# Power.net
KiCad netlist of a schematic drawn in Altium Designer
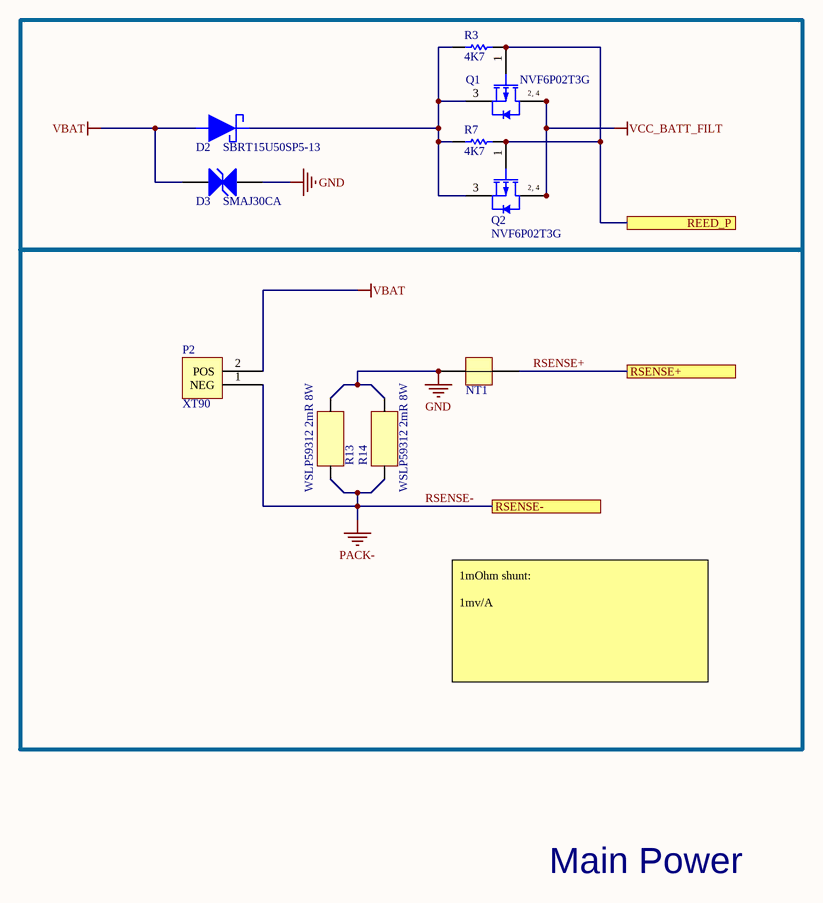
[diagram p0: Power.SchDoc]

(export (version "E")
  (design (tool "Eeschema 10.0.6"))
  (components
    (comp (ref "D2")
      (value "SBRT15U50SP5-13")
      (footprint "SBRT15U50SP5-13")
      (fields (field (name "MANUFACTURER") "Diodes Incorporated"))
      (libsource (lib "CMR_Miscellaneous_Devices") (part "SBRT15U50SP5-13"))
    )
    (comp (ref "D3")
      (value "SMAJ30CA")
      (footprint "LFUS-DO-214AC-A-2_V")
      (description "Transient Voltage Suppression Diode, 30 V, -65 to 150 degC, 2-Pin SMD, RoHS, Tape and Reel")
      (fields (field (name "MANUFACTURER") "Littelfuse-Inc."))
      (libsource (lib "Altium Content Vault") (part "DZEN-AA-2"))
    )
    (comp (ref "NT1")
      (value "Net Tie")
      (footprint "Net_Tie_80mil")
      (description "Use to tie together nets")
      (libsource (lib "CMR_PCB_Components") (part "Net Tie"))
    )
    (comp (ref "P2") (value "XT90") (footprint "XT90") (libsource (lib "Tauv-Lib") (part "XT90")))
    (comp (ref "Q1")
      (value "NVF6P02T3G")
      (footprint "ONSC-SOT-223-4-318E-04_V")
      (description "Power MOSFET, -10 A, -20 V, P-Channel, 4-Pin SOT-223, Pb-Free, Tape and Reel")
      (fields (field (name "MANUFACTURER") "On Semiconductor"))
      (libsource (lib "Altium Content Vault") (part "ONSC-PMOS-G1D2S3D4-4_B"))
    )
    (comp (ref "Q2")
      (value "NVF6P02T3G")
      (footprint "ONSC-SOT-223-4-318E-04_V")
      (description "Power MOSFET, -10 A, -20 V, P-Channel, 4-Pin SOT-223, Pb-Free, Tape and Reel")
      (fields (field (name "MANUFACTURER") "On Semiconductor"))
      (libsource (lib "Altium Content Vault") (part "ONSC-PMOS-G1D2S3D4-4_B"))
    )
    (comp (ref "R3")
      (value "4K7")
      (footprint "RESC0603(1608)_L")
      (description "4K7 0.1W 1% 0603 (1608 Metric)  SMD")
      (fields (field (name "POWER") "0.1 W") (field (name "TOLERANCE") "1 %"))
      (libsource (lib "Altium Content Vault") (part "RES"))
    )
    (comp (ref "R7")
      (value "4K7")
      (footprint "RESC0603(1608)_L")
      (description "4K7 0.1W 1% 0603 (1608 Metric)  SMD")
      (fields (field (name "POWER") "0.1 W") (field (name "TOLERANCE") "1 %"))
      (libsource (lib "Altium Content Vault") (part "RES"))
    )
    (comp (ref "R13")
      (value "WSLP59312 2mR 8W")
      (footprint "WSLP59312L000FEA")
      (libsource (lib "Tauv-Lib") (part "WSLP59312L000FEA"))
    )
    (comp (ref "R14")
      (value "WSLP59312 2mR 8W")
      (footprint "WSLP59312L000FEA")
      (libsource (lib "Tauv-Lib") (part "WSLP59312L000FEA"))
    )
  )
  (nets
    (net (code "1") (name "/REED_P") (class "Default")
      (node (ref "Q1") (pin "1") (pinfunction "G_1") (pintype "passive"))
      (node (ref "Q2") (pin "1") (pinfunction "G_1") (pintype "passive"))
      (node (ref "R3") (pin "1") (pinfunction "1_1") (pintype "passive"))
      (node (ref "R7") (pin "1") (pinfunction "1_1") (pintype "passive"))
    )
    (net (code "2") (name "/RSENSE+") (class "Default")
      (node (ref "NT1") (pin "2") (pinfunction "2_2") (pintype "passive"))
    )
    (net (code "3") (name "GND") (class "Default")
      (node (ref "D3") (pin "2") (pinfunction "A_2") (pintype "passive"))
      (node (ref "NT1") (pin "1") (pinfunction "1_1") (pintype "passive"))
      (node (ref "R13") (pin "2") (pinfunction "2_2") (pintype "passive"))
      (node (ref "R14") (pin "2") (pinfunction "2_2") (pintype "passive"))
    )
    (net (code "4") (name "Net-(Q1-S)") (class "Default")
      (node (ref "D2") (pin "2") (pinfunction "2_2") (pintype "passive"))
      (node (ref "Q1") (pin "3") (pinfunction "S_3") (pintype "passive"))
      (node (ref "Q2") (pin "3") (pinfunction "S_3") (pintype "passive"))
      (node (ref "R3") (pin "2") (pinfunction "2_2") (pintype "passive"))
      (node (ref "R7") (pin "2") (pinfunction "2_2") (pintype "passive"))
    )
    (net (code "5") (name "PACK-") (class "Default")
      (node (ref "P2") (pin "1") (pinfunction "NEG_1") (pintype "passive"))
      (node (ref "R13") (pin "1") (pinfunction "1_1") (pintype "passive"))
      (node (ref "R14") (pin "1") (pinfunction "1_1") (pintype "passive"))
    )
    (net (code "6") (name "VBAT") (class "Default")
      (node (ref "D2") (pin "1") (pinfunction "1_1") (pintype "passive"))
      (node (ref "D3") (pin "1") (pinfunction "A_1") (pintype "passive"))
      (node (ref "P2") (pin "2") (pinfunction "POS_2") (pintype "passive"))
    )
    (net (code "7") (name "VCC_BATT_FILT") (class "Default")
      (node (ref "Q1") (pin "2") (pinfunction "D_2") (pintype "passive"))
      (node (ref "Q1") (pin "4") (pinfunction "D_4") (pintype "passive"))
      (node (ref "Q2") (pin "2") (pinfunction "D_2") (pintype "passive"))
      (node (ref "Q2") (pin "4") (pinfunction "D_4") (pintype "passive"))
    )
  )
)
